# pca64110.net
KiCad netlist of a schematic drawn in Altium Designer
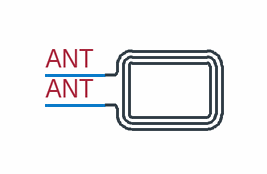
[diagram p0: pca64110.SchDoc]

(export (version "E")
  (design (tool "Eeschema 10.0.6"))
  (components
    (comp (ref "A1")
      (value "NFC_ANT_Listener-6")
      (footprint "NFC_ANT_Listener-6")
      (description "NFC Antenna Listener-6")
      (fields (field (name "MANUFACTURER") "N.A.") (field (name "AUTHOR") "rsk"))
      (libsource (lib "AltiumLib") (part "NFC_Antenna"))
    )
  )
  (nets
    (net (code "1") (name "/ANT") (class "Default")
      (node (ref "A1") (pin "1") (pinfunction "1_1") (pintype "passive"))
      (node (ref "A1") (pin "2") (pinfunction "2_2") (pintype "passive"))
    )
  )
)
